# 8_channel_relay_module.net
KiCad netlist of a schematic drawn in EAGLE
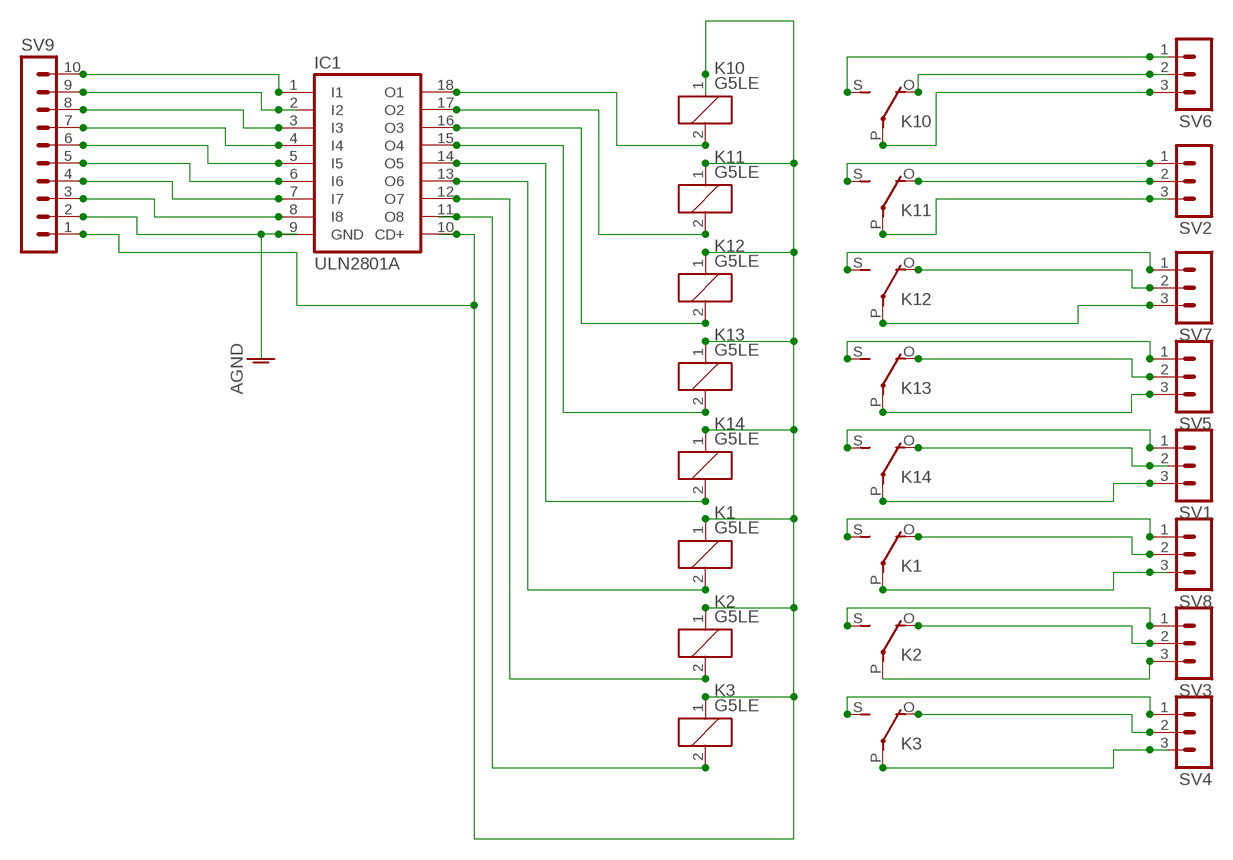
[diagram p0: schematic, sheet 1]

(export (version "E")
  (design (tool "Eeschema 10.0.6"))
  (components
    (comp (ref "IC1")
      (value "ULN2801A")
      (footprint "eagle-import:DIL18")
      (libsource (lib "eagle-import") (part "ULN2801A"))
    )
    (comp (ref "K1")
      (value "G5LE")
      (footprint "eagle-import:G5LE")
      (libsource (lib "eagle-import") (part "G5LE"))
    )
    (comp (ref "K2")
      (value "G5LE")
      (footprint "eagle-import:G5LE")
      (libsource (lib "eagle-import") (part "G5LE"))
    )
    (comp (ref "K3")
      (value "G5LE")
      (footprint "eagle-import:G5LE")
      (libsource (lib "eagle-import") (part "G5LE"))
    )
    (comp (ref "K10")
      (value "G5LE")
      (footprint "eagle-import:G5LE")
      (libsource (lib "eagle-import") (part "G5LE"))
    )
    (comp (ref "K11")
      (value "G5LE")
      (footprint "eagle-import:G5LE")
      (libsource (lib "eagle-import") (part "G5LE"))
    )
    (comp (ref "K12")
      (value "G5LE")
      (footprint "eagle-import:G5LE")
      (libsource (lib "eagle-import") (part "G5LE"))
    )
    (comp (ref "K13")
      (value "G5LE")
      (footprint "eagle-import:G5LE")
      (libsource (lib "eagle-import") (part "G5LE"))
    )
    (comp (ref "K14")
      (value "G5LE")
      (footprint "eagle-import:G5LE")
      (libsource (lib "eagle-import") (part "G5LE"))
    )
    (comp (ref "SV1")
      (value "MA03-1")
      (footprint "eagle-import:MA03-1")
      (libsource (lib "eagle-import") (part "MA03-1"))
    )
    (comp (ref "SV2")
      (value "MA03-1")
      (footprint "eagle-import:MA03-1")
      (libsource (lib "eagle-import") (part "MA03-1"))
    )
    (comp (ref "SV3")
      (value "MA03-1")
      (footprint "eagle-import:MA03-1")
      (libsource (lib "eagle-import") (part "MA03-1"))
    )
    (comp (ref "SV4")
      (value "MA03-1")
      (footprint "eagle-import:MA03-1")
      (libsource (lib "eagle-import") (part "MA03-1"))
    )
    (comp (ref "SV5")
      (value "MA03-1")
      (footprint "eagle-import:MA03-1")
      (libsource (lib "eagle-import") (part "MA03-1"))
    )
    (comp (ref "SV6")
      (value "MA03-1")
      (footprint "eagle-import:MA03-1")
      (libsource (lib "eagle-import") (part "MA03-1"))
    )
    (comp (ref "SV7")
      (value "MA03-1")
      (footprint "eagle-import:MA03-1")
      (libsource (lib "eagle-import") (part "MA03-1"))
    )
    (comp (ref "SV8")
      (value "MA03-1")
      (footprint "eagle-import:MA03-1")
      (libsource (lib "eagle-import") (part "MA03-1"))
    )
    (comp (ref "SV9")
      (value "MA10-1")
      (footprint "eagle-import:MA10-1")
      (libsource (lib "eagle-import") (part "MA10-1"))
    )
  )
  (nets
    (net (code "2") (name "Net-(IC1-CD+)") (class "Default")
      (node (ref "IC1") (pin "10") (pinfunction "CD+_10") (pintype "passive"))
      (node (ref "K1") (pin "1") (pinfunction "1_1") (pintype "passive"))
      (node (ref "K10") (pin "1") (pinfunction "1_1") (pintype "passive"))
      (node (ref "K11") (pin "1") (pinfunction "1_1") (pintype "passive"))
      (node (ref "K12") (pin "1") (pinfunction "1_1") (pintype "passive"))
      (node (ref "K13") (pin "1") (pinfunction "1_1") (pintype "passive"))
      (node (ref "K14") (pin "1") (pinfunction "1_1") (pintype "passive"))
      (node (ref "K2") (pin "1") (pinfunction "1_1") (pintype "passive"))
      (node (ref "K3") (pin "1") (pinfunction "1_1") (pintype "passive"))
      (node (ref "SV9") (pin "1") (pinfunction "1_1") (pintype "passive"))
    )
    (net (code "3") (name "Net-(IC1-GND)") (class "Default")
      (node (ref "IC1") (pin "9") (pinfunction "GND_9") (pintype "power_in"))
      (node (ref "SV9") (pin "2") (pinfunction "2_2") (pintype "passive"))
    )
    (net (code "4") (name "Net-(IC1-I1)") (class "Default")
      (node (ref "IC1") (pin "1") (pinfunction "I1_1") (pintype "input"))
      (node (ref "SV9") (pin "10") (pinfunction "10_10") (pintype "passive"))
    )
    (net (code "5") (name "Net-(IC1-I2)") (class "Default")
      (node (ref "IC1") (pin "2") (pinfunction "I2_2") (pintype "input"))
      (node (ref "SV9") (pin "9") (pinfunction "9_9") (pintype "passive"))
    )
    (net (code "6") (name "Net-(IC1-I3)") (class "Default")
      (node (ref "IC1") (pin "3") (pinfunction "I3_3") (pintype "input"))
      (node (ref "SV9") (pin "8") (pinfunction "8_8") (pintype "passive"))
    )
    (net (code "7") (name "Net-(IC1-I4)") (class "Default")
      (node (ref "IC1") (pin "4") (pinfunction "I4_4") (pintype "input"))
      (node (ref "SV9") (pin "7") (pinfunction "7_7") (pintype "passive"))
    )
    (net (code "8") (name "Net-(IC1-I5)") (class "Default")
      (node (ref "IC1") (pin "5") (pinfunction "I5_5") (pintype "input"))
      (node (ref "SV9") (pin "6") (pinfunction "6_6") (pintype "passive"))
    )
    (net (code "9") (name "Net-(IC1-I6)") (class "Default")
      (node (ref "IC1") (pin "6") (pinfunction "I6_6") (pintype "input"))
      (node (ref "SV9") (pin "5") (pinfunction "5_5") (pintype "passive"))
    )
    (net (code "10") (name "Net-(IC1-I7)") (class "Default")
      (node (ref "IC1") (pin "7") (pinfunction "I7_7") (pintype "input"))
      (node (ref "SV9") (pin "4") (pinfunction "4_4") (pintype "passive"))
    )
    (net (code "11") (name "Net-(IC1-I8)") (class "Default")
      (node (ref "IC1") (pin "8") (pinfunction "I8_8") (pintype "input"))
      (node (ref "SV9") (pin "3") (pinfunction "3_3") (pintype "passive"))
    )
    (net (code "12") (name "Net-(IC1-O1)") (class "Default")
      (node (ref "IC1") (pin "18") (pinfunction "O1_18") (pintype "open_collector"))
      (node (ref "K10") (pin "2") (pinfunction "2_2") (pintype "passive"))
    )
    (net (code "13") (name "Net-(IC1-O2)") (class "Default")
      (node (ref "IC1") (pin "17") (pinfunction "O2_17") (pintype "open_collector"))
      (node (ref "K11") (pin "2") (pinfunction "2_2") (pintype "passive"))
    )
    (net (code "14") (name "Net-(IC1-O3)") (class "Default")
      (node (ref "IC1") (pin "16") (pinfunction "O3_16") (pintype "open_collector"))
      (node (ref "K12") (pin "2") (pinfunction "2_2") (pintype "passive"))
    )
    (net (code "15") (name "Net-(IC1-O4)") (class "Default")
      (node (ref "IC1") (pin "15") (pinfunction "O4_15") (pintype "open_collector"))
      (node (ref "K13") (pin "2") (pinfunction "2_2") (pintype "passive"))
    )
    (net (code "16") (name "Net-(IC1-O5)") (class "Default")
      (node (ref "IC1") (pin "14") (pinfunction "O5_14") (pintype "open_collector"))
      (node (ref "K14") (pin "2") (pinfunction "2_2") (pintype "passive"))
    )
    (net (code "17") (name "Net-(IC1-O6)") (class "Default")
      (node (ref "IC1") (pin "13") (pinfunction "O6_13") (pintype "open_collector"))
      (node (ref "K1") (pin "2") (pinfunction "2_2") (pintype "passive"))
    )
    (net (code "18") (name "Net-(IC1-O7)") (class "Default")
      (node (ref "IC1") (pin "12") (pinfunction "O7_12") (pintype "open_collector"))
      (node (ref "K2") (pin "2") (pinfunction "2_2") (pintype "passive"))
    )
    (net (code "19") (name "Net-(IC1-O8)") (class "Default")
      (node (ref "IC1") (pin "11") (pinfunction "O8_11") (pintype "open_collector"))
      (node (ref "K3") (pin "2") (pinfunction "2_2") (pintype "passive"))
    )
    (net (code "20") (name "Net-(K1-PadO)") (class "Default")
      (node (ref "K1") (pin "O") (pinfunction "O_O") (pintype "passive"))
      (node (ref "SV8") (pin "2") (pinfunction "2_2") (pintype "passive"))
    )
    (net (code "21") (name "Net-(K1-PadP)") (class "Default")
      (node (ref "K1") (pin "P") (pinfunction "P_P") (pintype "passive"))
      (node (ref "SV8") (pin "3") (pinfunction "3_3") (pintype "passive"))
    )
    (net (code "22") (name "Net-(K1-PadS)") (class "Default")
      (node (ref "K1") (pin "S") (pinfunction "S_S") (pintype "passive"))
      (node (ref "SV8") (pin "1") (pinfunction "1_1") (pintype "passive"))
    )
    (net (code "23") (name "Net-(K2-PadO)") (class "Default")
      (node (ref "K2") (pin "O") (pinfunction "O_O") (pintype "passive"))
      (node (ref "SV3") (pin "2") (pinfunction "2_2") (pintype "passive"))
    )
    (net (code "24") (name "Net-(K2-PadP)") (class "Default")
      (node (ref "K2") (pin "P") (pinfunction "P_P") (pintype "passive"))
      (node (ref "SV3") (pin "3") (pinfunction "3_3") (pintype "passive"))
    )
    (net (code "25") (name "Net-(K2-PadS)") (class "Default")
      (node (ref "K2") (pin "S") (pinfunction "S_S") (pintype "passive"))
      (node (ref "SV3") (pin "1") (pinfunction "1_1") (pintype "passive"))
    )
    (net (code "26") (name "Net-(K3-PadO)") (class "Default")
      (node (ref "K3") (pin "O") (pinfunction "O_O") (pintype "passive"))
      (node (ref "SV4") (pin "2") (pinfunction "2_2") (pintype "passive"))
    )
    (net (code "27") (name "Net-(K3-PadP)") (class "Default")
      (node (ref "K3") (pin "P") (pinfunction "P_P") (pintype "passive"))
      (node (ref "SV4") (pin "3") (pinfunction "3_3") (pintype "passive"))
    )
    (net (code "28") (name "Net-(K3-PadS)") (class "Default")
      (node (ref "K3") (pin "S") (pinfunction "S_S") (pintype "passive"))
      (node (ref "SV4") (pin "1") (pinfunction "1_1") (pintype "passive"))
    )
    (net (code "29") (name "Net-(K10-PadO)") (class "Default")
      (node (ref "K10") (pin "O") (pinfunction "O_O") (pintype "passive"))
      (node (ref "SV6") (pin "2") (pinfunction "2_2") (pintype "passive"))
    )
    (net (code "30") (name "Net-(K10-PadP)") (class "Default")
      (node (ref "K10") (pin "P") (pinfunction "P_P") (pintype "passive"))
      (node (ref "SV6") (pin "3") (pinfunction "3_3") (pintype "passive"))
    )
    (net (code "31") (name "Net-(K10-PadS)") (class "Default")
      (node (ref "K10") (pin "S") (pinfunction "S_S") (pintype "passive"))
      (node (ref "SV6") (pin "1") (pinfunction "1_1") (pintype "passive"))
    )
    (net (code "32") (name "Net-(K11-PadO)") (class "Default")
      (node (ref "K11") (pin "O") (pinfunction "O_O") (pintype "passive"))
      (node (ref "SV2") (pin "2") (pinfunction "2_2") (pintype "passive"))
    )
    (net (code "33") (name "Net-(K11-PadP)") (class "Default")
      (node (ref "K11") (pin "P") (pinfunction "P_P") (pintype "passive"))
      (node (ref "SV2") (pin "3") (pinfunction "3_3") (pintype "passive"))
    )
    (net (code "34") (name "Net-(K11-PadS)") (class "Default")
      (node (ref "K11") (pin "S") (pinfunction "S_S") (pintype "passive"))
      (node (ref "SV2") (pin "1") (pinfunction "1_1") (pintype "passive"))
    )
    (net (code "35") (name "Net-(K12-PadO)") (class "Default")
      (node (ref "K12") (pin "O") (pinfunction "O_O") (pintype "passive"))
      (node (ref "SV7") (pin "2") (pinfunction "2_2") (pintype "passive"))
    )
    (net (code "36") (name "Net-(K12-PadP)") (class "Default")
      (node (ref "K12") (pin "P") (pinfunction "P_P") (pintype "passive"))
      (node (ref "SV7") (pin "3") (pinfunction "3_3") (pintype "passive"))
    )
    (net (code "37") (name "Net-(K12-PadS)") (class "Default")
      (node (ref "K12") (pin "S") (pinfunction "S_S") (pintype "passive"))
      (node (ref "SV7") (pin "1") (pinfunction "1_1") (pintype "passive"))
    )
    (net (code "38") (name "Net-(K13-PadO)") (class "Default")
      (node (ref "K13") (pin "O") (pinfunction "O_O") (pintype "passive"))
      (node (ref "SV5") (pin "2") (pinfunction "2_2") (pintype "passive"))
    )
    (net (code "39") (name "Net-(K13-PadP)") (class "Default")
      (node (ref "K13") (pin "P") (pinfunction "P_P") (pintype "passive"))
      (node (ref "SV5") (pin "3") (pinfunction "3_3") (pintype "passive"))
    )
    (net (code "40") (name "Net-(K13-PadS)") (class "Default")
      (node (ref "K13") (pin "S") (pinfunction "S_S") (pintype "passive"))
      (node (ref "SV5") (pin "1") (pinfunction "1_1") (pintype "passive"))
    )
    (net (code "41") (name "Net-(K14-PadO)") (class "Default")
      (node (ref "K14") (pin "O") (pinfunction "O_O") (pintype "passive"))
      (node (ref "SV1") (pin "2") (pinfunction "2_2") (pintype "passive"))
    )
    (net (code "42") (name "Net-(K14-PadP)") (class "Default")
      (node (ref "K14") (pin "P") (pinfunction "P_P") (pintype "passive"))
      (node (ref "SV1") (pin "3") (pinfunction "3_3") (pintype "passive"))
    )
    (net (code "43") (name "Net-(K14-PadS)") (class "Default")
      (node (ref "K14") (pin "S") (pinfunction "S_S") (pintype "passive"))
      (node (ref "SV1") (pin "1") (pinfunction "1_1") (pintype "passive"))
    )
  )
)
